# basic_attiny84.net
KiCad netlist of a schematic drawn in EAGLE
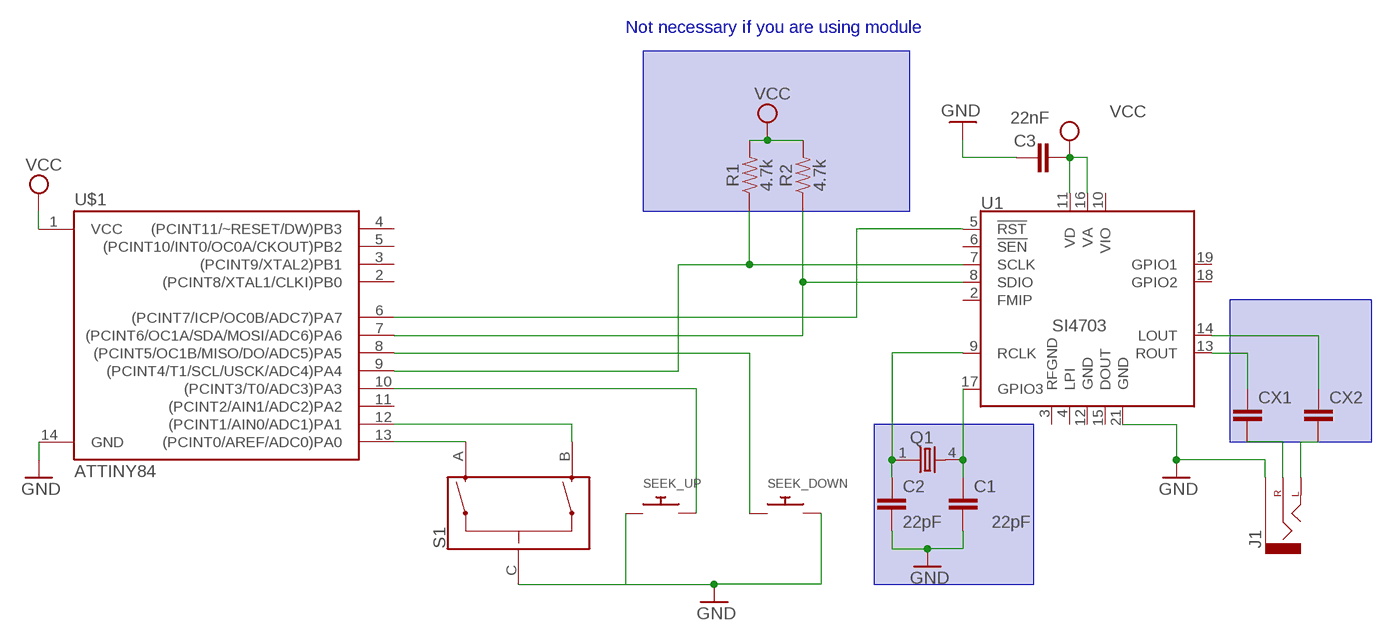
[diagram p0: schematic, sheet 1]

(export (version "E")
  (design (tool "Eeschema 10.0.6"))
  (components
    (comp (ref "C1")
      (value "22pF")
      (footprint "eagle-import:C2.5-3")
      (libsource (lib "eagle-import") (part "C2,5-3"))
    )
    (comp (ref "C2")
      (value "22pF")
      (footprint "eagle-import:C2.5-3")
      (libsource (lib "eagle-import") (part "C2,5-3"))
    )
    (comp (ref "C3")
      (value "22nF")
      (footprint "eagle-import:C2.5-3")
      (libsource (lib "eagle-import") (part "C2,5-3"))
    )
    (comp (ref "CX1")
      (value "CXXC10B6")
      (footprint "eagle-import:XC10B6")
      (libsource (lib "eagle-import") (part "CXXC10B6"))
    )
    (comp (ref "CX2")
      (value "CXXC10B6")
      (footprint "eagle-import:XC10B6")
      (libsource (lib "eagle-import") (part "CXXC10B6"))
    )
    (comp (ref "J1")
      (value "AUDIO_JACK_2.5MM_HOLESONLY")
      (footprint "eagle-import:STEREOJACK2.5MM_SPECIAL_HOLES-ONLY")
      (libsource (lib "eagle-import") (part "AUDIO_JACK_2.5MM_HOLESONLY"))
    )
    (comp (ref "Q1")
      (value "86SMX")
      (footprint "eagle-import:86SMX")
      (fields (field (name "MF") "C-MAC  FREQUENCY PRODUCTS LTD") (field (name "MPN") "XTAL003321- 86SMX"))
      (libsource (lib "eagle-import") (part "86SMX"))
    )
    (comp (ref "R1")
      (value "4.7k")
      (footprint "eagle-import:0603")
      (libsource (lib "eagle-import") (part "4.7KOHM-0603-1/10W-1%"))
    )
    (comp (ref "R2")
      (value "4.7k")
      (footprint "eagle-import:0603")
      (libsource (lib "eagle-import") (part "4.7KOHM-0603-1/10W-1%"))
    )
    (comp (ref "S1")
      (value "ENCODER")
      (footprint "eagle-import:ENCODER-16MM-QUAD")
      (libsource (lib "eagle-import") (part "ENCODER"))
    )
    (comp (ref "SEEK_DOWN")
      (value "SWITCH_PUSHBUTTONC&K_KSS")
      (footprint "eagle-import:BTN_CK_KSS")
      (libsource (lib "eagle-import") (part "SWITCH_PUSHBUTTONC&K_KSS"))
    )
    (comp (ref "SEEK_UP")
      (value "SWITCH_PUSHBUTTONC&K_KSS")
      (footprint "eagle-import:BTN_CK_KSS")
      (libsource (lib "eagle-import") (part "SWITCH_PUSHBUTTONC&K_KSS"))
    )
    (comp (ref "U$1")
      (value "ATTINY84")
      (footprint "eagle-import:SO14")
      (libsource (lib "eagle-import") (part "ATTINY84"))
    )
    (comp (ref "U1")
      (value "SI4703")
      (footprint "eagle-import:QFN-20-3X3MM")
      (fields (field (name "MF") "SparkFun Electronics"))
      (libsource (lib "eagle-import") (part "SI4703"))
    )
  )
  (nets
    (net (code "1") (name "GND") (class "Default")
      (node (ref "C1") (pin "2") (pinfunction "2_2") (pintype "passive"))
      (node (ref "C2") (pin "2") (pinfunction "2_2") (pintype "passive"))
      (node (ref "C3") (pin "1") (pinfunction "1_1") (pintype "passive"))
      (node (ref "J1") (pin "RING1") (pinfunction "SLEEVE_RING1") (pintype "bidirectional"))
      (node (ref "S1") (pin "C") (pinfunction "C_C") (pintype "bidirectional"))
      (node (ref "SEEK_DOWN") (pin "P$2") (pinfunction "P$2_P$2") (pintype "passive"))
      (node (ref "SEEK_UP") (pin "P$1") (pinfunction "P$1_P$1") (pintype "passive"))
      (node (ref "U$1") (pin "14") (pinfunction "GND_14") (pintype "bidirectional"))
      (node (ref "U1") (pin "21") (pinfunction "GND_21") (pintype "bidirectional"))
    )
    (net (code "2") (name "Net-(J1-LEFT)") (class "Default")
      (node (ref "CX2") (pin "2") (pinfunction "2_2") (pintype "passive"))
      (node (ref "J1") (pin "SHIELD") (pinfunction "LEFT_SHIELD") (pintype "bidirectional"))
    )
    (net (code "3") (name "Net-(J1-RIGHT)") (class "Default")
      (node (ref "CX1") (pin "2") (pinfunction "2_2") (pintype "passive"))
      (node (ref "J1") (pin "TIP") (pinfunction "RIGHT_TIP") (pintype "bidirectional"))
    )
    (net (code "4") (name "Net-(Q1-2)") (class "Default")
      (node (ref "C1") (pin "1") (pinfunction "1_1") (pintype "passive"))
      (node (ref "Q1") (pin "4") (pinfunction "2_4") (pintype "passive"))
      (node (ref "U1") (pin "17") (pinfunction "GPIO3_17") (pintype "bidirectional"))
    )
    (net (code "5") (name "Net-(U$1-(PCINT0{slash}AREF{slash}ADC0)PA0)") (class "Default")
      (node (ref "S1") (pin "A") (pinfunction "A_A") (pintype "bidirectional"))
      (node (ref "U$1") (pin "13") (pinfunction "(PCINT0/AREF/ADC0)PA0_13") (pintype "bidirectional"))
    )
    (net (code "6") (name "Net-(U$1-(PCINT1{slash}AIN0{slash}ADC1)PA1)") (class "Default")
      (node (ref "S1") (pin "B") (pinfunction "B_B") (pintype "bidirectional"))
      (node (ref "U$1") (pin "12") (pinfunction "(PCINT1/AIN0/ADC1)PA1_12") (pintype "bidirectional"))
    )
    (net (code "7") (name "Net-(U$1-(PCINT3{slash}T0{slash}ADC3)PA3)") (class "Default")
      (node (ref "SEEK_UP") (pin "P$2") (pinfunction "P$2_P$2") (pintype "passive"))
      (node (ref "U$1") (pin "10") (pinfunction "(PCINT3/T0/ADC3)PA3_10") (pintype "bidirectional"))
    )
    (net (code "8") (name "Net-(U$1-(PCINT4{slash}T1{slash}SCL{slash}USCK{slash}ADC4)PA4)") (class "Default")
      (node (ref "R1") (pin "1") (pinfunction "1_1") (pintype "passive"))
      (node (ref "U$1") (pin "9") (pinfunction "(PCINT4/T1/SCL/USCK/ADC4)PA4_9") (pintype "bidirectional"))
      (node (ref "U1") (pin "7") (pinfunction "SCLK_7") (pintype "bidirectional"))
    )
    (net (code "9") (name "Net-(U$1-(PCINT5{slash}OC1B{slash}MISO{slash}DO{slash}ADC5)PA5)") (class "Default")
      (node (ref "SEEK_DOWN") (pin "P$1") (pinfunction "P$1_P$1") (pintype "passive"))
      (node (ref "U$1") (pin "8") (pinfunction "(PCINT5/OC1B/MISO/DO/ADC5)PA5_8") (pintype "bidirectional"))
    )
    (net (code "10") (name "Net-(U$1-(PCINT6{slash}OC1A{slash}SDA{slash}MOSI{slash}ADC6)PA6)") (class "Default")
      (node (ref "R2") (pin "1") (pinfunction "1_1") (pintype "passive"))
      (node (ref "U$1") (pin "7") (pinfunction "(PCINT6/OC1A/SDA/MOSI/ADC6)PA6_7") (pintype "bidirectional"))
      (node (ref "U1") (pin "8") (pinfunction "SDIO_8") (pintype "bidirectional"))
    )
    (net (code "11") (name "Net-(U$1-(PCINT7{slash}ICP{slash}OC0B{slash}ADC7)PA7)") (class "Default")
      (node (ref "U$1") (pin "6") (pinfunction "(PCINT7/ICP/OC0B/ADC7)PA7_6") (pintype "bidirectional"))
      (node (ref "U1") (pin "5") (pinfunction "~{RST}_5") (pintype "bidirectional"))
    )
    (net (code "12") (name "Net-(U1-LOUT)") (class "Default")
      (node (ref "CX2") (pin "1") (pinfunction "1_1") (pintype "passive"))
      (node (ref "U1") (pin "14") (pinfunction "LOUT_14") (pintype "bidirectional"))
    )
    (net (code "13") (name "Net-(U1-RCLK)") (class "Default")
      (node (ref "C2") (pin "1") (pinfunction "1_1") (pintype "passive"))
      (node (ref "Q1") (pin "1") (pinfunction "1_1") (pintype "passive"))
      (node (ref "U1") (pin "9") (pinfunction "RCLK_9") (pintype "bidirectional"))
    )
    (net (code "14") (name "Net-(U1-ROUT)") (class "Default")
      (node (ref "CX1") (pin "1") (pinfunction "1_1") (pintype "passive"))
      (node (ref "U1") (pin "13") (pinfunction "ROUT_13") (pintype "bidirectional"))
    )
    (net (code "15") (name "VCC") (class "Default")
      (node (ref "C3") (pin "2") (pinfunction "2_2") (pintype "passive"))
      (node (ref "R1") (pin "2") (pinfunction "2_2") (pintype "passive"))
      (node (ref "R2") (pin "2") (pinfunction "2_2") (pintype "passive"))
      (node (ref "U$1") (pin "1") (pinfunction "VCC_1") (pintype "bidirectional"))
      (node (ref "U1") (pin "11") (pinfunction "VD_11") (pintype "bidirectional"))
      (node (ref "U1") (pin "16") (pinfunction "VA_16") (pintype "bidirectional"))
    )
    (net (code "16") (name "unconnected-(U$1-(PCINT2{slash}AIN1{slash}ADC2)PA2-Pad11)") (class "Default")
      (node (ref "U$1") (pin "11") (pinfunction "(PCINT2/AIN1/ADC2)PA2_11") (pintype "bidirectional"))
    )
    (net (code "17") (name "unconnected-(U$1-(PCINT8{slash}XTAL1{slash}CLKI)PB0-Pad2)") (class "Default")
      (node (ref "U$1") (pin "2") (pinfunction "(PCINT8/XTAL1/CLKI)PB0_2") (pintype "bidirectional"))
    )
    (net (code "18") (name "unconnected-(U$1-(PCINT9{slash}XTAL2)PB1-Pad3)") (class "Default")
      (node (ref "U$1") (pin "3") (pinfunction "(PCINT9/XTAL2)PB1_3") (pintype "bidirectional"))
    )
    (net (code "19") (name "unconnected-(U$1-(PCINT10{slash}INT0{slash}OC0A{slash}CKOUT)PB2-Pad5)") (class "Default")
      (node (ref "U$1") (pin "5") (pinfunction "(PCINT10/INT0/OC0A/CKOUT)PB2_5") (pintype "bidirectional"))
    )
    (net (code "20") (name "unconnected-(U$1-(PCINT11{slash}~{RESET{slash}DW})PB3-Pad4)") (class "Default")
      (node (ref "U$1") (pin "4") (pinfunction "(PCINT11/~{RESET/DW})PB3_4") (pintype "bidirectional"))
    )
    (net (code "21") (name "unconnected-(U1-DOUT-Pad15)") (class "Default")
      (node (ref "U1") (pin "15") (pinfunction "DOUT_15") (pintype "bidirectional"))
    )
    (net (code "22") (name "unconnected-(U1-FMIP-Pad2)") (class "Default")
      (node (ref "U1") (pin "2") (pinfunction "FMIP_2") (pintype "bidirectional"))
    )
    (net (code "23") (name "unconnected-(U1-GND-Pad12)") (class "Default")
      (node (ref "U1") (pin "12") (pinfunction "GND_12") (pintype "bidirectional"))
    )
    (net (code "24") (name "unconnected-(U1-GPIO1-Pad19)") (class "Default")
      (node (ref "U1") (pin "19") (pinfunction "GPIO1_19") (pintype "bidirectional"))
    )
    (net (code "25") (name "unconnected-(U1-GPIO2-Pad18)") (class "Default")
      (node (ref "U1") (pin "18") (pinfunction "GPIO2_18") (pintype "bidirectional"))
    )
    (net (code "26") (name "unconnected-(U1-LPI-Pad4)") (class "Default")
      (node (ref "U1") (pin "4") (pinfunction "LPI_4") (pintype "bidirectional"))
    )
    (net (code "27") (name "unconnected-(U1-RFGND-Pad3)") (class "Default")
      (node (ref "U1") (pin "3") (pinfunction "RFGND_3") (pintype "bidirectional"))
    )
    (net (code "28") (name "unconnected-(U1-VIO-Pad10)") (class "Default")
      (node (ref "U1") (pin "10") (pinfunction "VIO_10") (pintype "bidirectional"))
    )
    (net (code "29") (name "unconnected-(U1-~{SEN}-Pad6)") (class "Default")
      (node (ref "U1") (pin "6") (pinfunction "~{SEN}_6") (pintype "bidirectional"))
    )
  )
)
